# MotorCtrl.net
KiCad netlist of a schematic drawn in Altium Designer
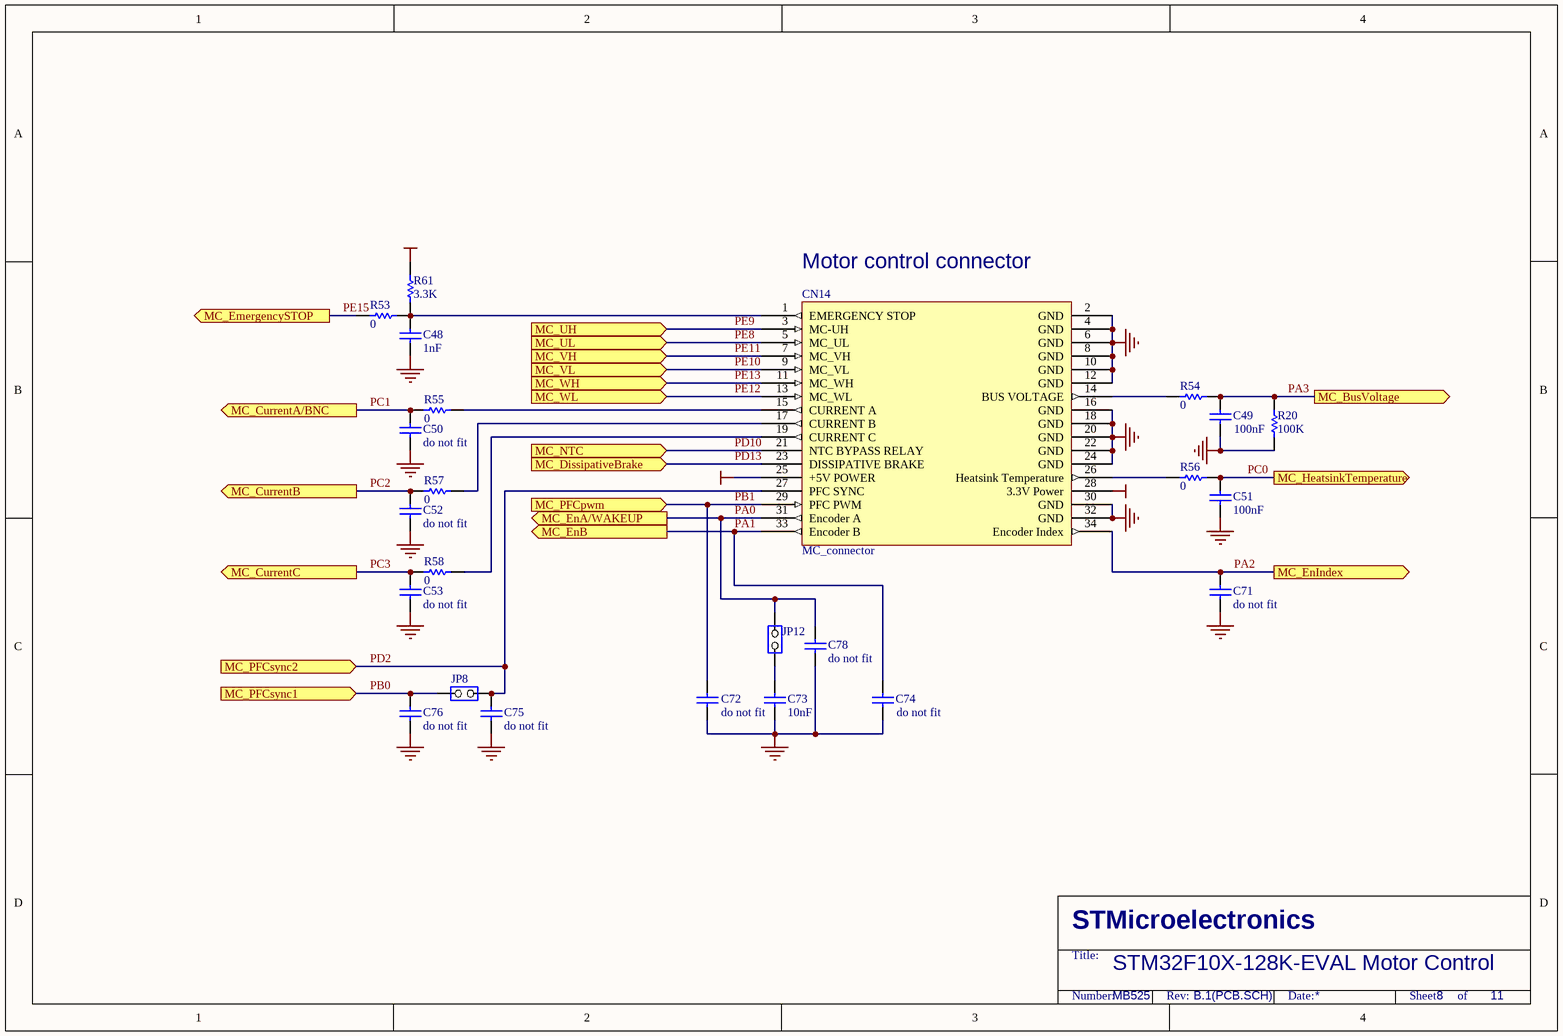
[diagram p0: MotorCtrl.SchDoc]

(export (version "E")
  (design (tool "Eeschema 10.0.6"))
  (components
    (comp (ref "C48")
      (value "1nF")
      (description "Capacitor")
      (fields (field (name "PUBLISHER") "Altium Limited"))
      (libsource (lib "Miscellaneous Devices") (part "CAP"))
    )
    (comp (ref "C49")
      (value "100nF")
      (description "Capacitor")
      (fields (field (name "PUBLISHER") "Altium Limited"))
      (libsource (lib "Miscellaneous Devices") (part "cap"))
    )
    (comp (ref "C50")
      (value "do not fit")
      (description "Capacitor")
      (fields (field (name "PUBLISHER") "Altium Limited"))
      (libsource (lib "Miscellaneous Devices") (part "cap"))
    )
    (comp (ref "C51")
      (value "100nF")
      (description "Capacitor")
      (fields (field (name "PUBLISHER") "Altium Limited"))
      (libsource (lib "Miscellaneous Devices") (part "cap"))
    )
    (comp (ref "C52")
      (value "do not fit")
      (description "Capacitor")
      (fields (field (name "PUBLISHER") "Altium Limited"))
      (libsource (lib "Miscellaneous Devices") (part "cap"))
    )
    (comp (ref "C53")
      (value "do not fit")
      (description "Capacitor")
      (fields (field (name "PUBLISHER") "Altium Limited"))
      (libsource (lib "Miscellaneous Devices") (part "cap"))
    )
    (comp (ref "C71")
      (value "do not fit")
      (description "Capacitor")
      (fields (field (name "PUBLISHER") "Altium Limited"))
      (libsource (lib "Miscellaneous Devices") (part "cap"))
    )
    (comp (ref "C72")
      (value "do not fit")
      (description "Capacitor")
      (fields (field (name "PUBLISHER") "Altium Limited"))
      (libsource (lib "Miscellaneous Devices") (part "cap"))
    )
    (comp (ref "C73")
      (value "10nF")
      (description "Capacitor")
      (fields (field (name "PUBLISHER") "Altium Limited"))
      (libsource (lib "Miscellaneous Devices") (part "cap"))
    )
    (comp (ref "C74")
      (value "do not fit")
      (description "Capacitor")
      (fields (field (name "PUBLISHER") "Altium Limited"))
      (libsource (lib "Miscellaneous Devices") (part "cap"))
    )
    (comp (ref "C75")
      (value "do not fit")
      (description "Capacitor")
      (fields (field (name "PUBLISHER") "Altium Limited"))
      (libsource (lib "Miscellaneous Devices") (part "cap"))
    )
    (comp (ref "C76")
      (value "do not fit")
      (description "Capacitor")
      (fields (field (name "PUBLISHER") "Altium Limited"))
      (libsource (lib "Miscellaneous Devices") (part "cap"))
    )
    (comp (ref "C78")
      (value "do not fit")
      (description "Capacitor")
      (fields (field (name "PUBLISHER") "Altium Limited"))
      (libsource (lib "Miscellaneous Devices") (part "cap"))
    )
    (comp (ref "CN14")
      (value "MC_connector")
      (footprint "IDC34S")
      (libsource (lib "MB525") (part "MC_connector"))
    )
    (comp (ref "JP8") (value "~") (footprint "SIP2") (libsource (lib "*") (part "JP2")))
    (comp (ref "JP12") (value "~") (footprint "SIP2") (libsource (lib "*") (part "JP2")))
    (comp (ref "R20")
      (value "100K")
      (footprint "0603")
      (description "Resistor")
      (fields (field (name "PUBLISHER") "Altium Limited"))
      (libsource (lib "Miscellaneous Devices") (part "Res1"))
    )
    (comp (ref "R53")
      (value "0")
      (description "Resistor")
      (fields (field (name "PUBLISHER") "Altium Limited"))
      (libsource (lib "Miscellaneous Devices") (part "Res1"))
    )
    (comp (ref "R54")
      (value "0")
      (footprint "0603")
      (description "Resistor")
      (fields (field (name "PUBLISHER") "Altium Limited"))
      (libsource (lib "Miscellaneous Devices") (part "Res1"))
    )
    (comp (ref "R55")
      (value "0")
      (footprint "0603")
      (description "Resistor")
      (fields (field (name "PUBLISHER") "Altium Limited"))
      (libsource (lib "Miscellaneous Devices") (part "Res1"))
    )
    (comp (ref "R56")
      (value "0")
      (footprint "0603")
      (description "Resistor")
      (fields (field (name "PUBLISHER") "Altium Limited"))
      (libsource (lib "Miscellaneous Devices") (part "Res1"))
    )
    (comp (ref "R57")
      (value "0")
      (footprint "0603")
      (description "Resistor")
      (fields (field (name "PUBLISHER") "Altium Limited"))
      (libsource (lib "Miscellaneous Devices") (part "Res1"))
    )
    (comp (ref "R58")
      (value "0")
      (footprint "0603")
      (description "Resistor")
      (fields (field (name "PUBLISHER") "Altium Limited"))
      (libsource (lib "Miscellaneous Devices") (part "Res1"))
    )
    (comp (ref "R61")
      (value "3.3K")
      (description "Resistor")
      (fields (field (name "PUBLISHER") "Altium Limited"))
      (libsource (lib "Miscellaneous Devices") (part "Res1"))
    )
  )
  (nets
    (net (code "1") (name "+3V3") (class "Default")
      (node (ref "CN14") (pin "28") (pinfunction "3.3V_Power_28") (pintype "power_in"))
      (node (ref "R61") (pin "2") (pinfunction "2_2") (pintype "passive"))
    )
    (net (code "2") (name "+5V") (class "Default")
      (node (ref "CN14") (pin "25") (pinfunction "+5V_POWER_25") (pintype "power_in"))
    )
    (net (code "3") (name "/PA0") (class "Default")
      (node (ref "C78") (pin "2") (pinfunction "2_2") (pintype "passive"))
      (node (ref "CN14") (pin "31") (pinfunction "Encoder_A_31") (pintype "output"))
      (node (ref "JP12") (pin "1") (pinfunction "COMMON_1") (pintype "passive"))
    )
    (net (code "4") (name "/PA1") (class "Default")
      (node (ref "C74") (pin "2") (pinfunction "2_2") (pintype "passive"))
      (node (ref "CN14") (pin "33") (pinfunction "Encoder_B_33") (pintype "output"))
    )
    (net (code "5") (name "/PA2") (class "Default")
      (node (ref "C71") (pin "2") (pinfunction "2_2") (pintype "passive"))
      (node (ref "CN14") (pin "34") (pinfunction "Encoder_Index_34") (pintype "output"))
    )
    (net (code "6") (name "/PA3") (class "Default")
      (node (ref "C49") (pin "2") (pinfunction "2_2") (pintype "passive"))
      (node (ref "R20") (pin "2") (pinfunction "2_2") (pintype "passive"))
      (node (ref "R54") (pin "2") (pinfunction "2_2") (pintype "passive"))
    )
    (net (code "7") (name "/PB0") (class "Default")
      (node (ref "C76") (pin "2") (pinfunction "2_2") (pintype "passive"))
      (node (ref "JP8") (pin "2") (pinfunction "NO_2") (pintype "passive"))
    )
    (net (code "8") (name "/PB1") (class "Default")
      (node (ref "C72") (pin "2") (pinfunction "2_2") (pintype "passive"))
      (node (ref "CN14") (pin "29") (pinfunction "PFC_PWM_29") (pintype "input"))
    )
    (net (code "9") (name "/PC0") (class "Default")
      (node (ref "C51") (pin "2") (pinfunction "2_2") (pintype "passive"))
      (node (ref "R56") (pin "2") (pinfunction "2_2") (pintype "passive"))
    )
    (net (code "10") (name "/PC1") (class "Default")
      (node (ref "C50") (pin "2") (pinfunction "2_2") (pintype "passive"))
      (node (ref "R55") (pin "1") (pinfunction "1_1") (pintype "passive"))
    )
    (net (code "11") (name "/PC2") (class "Default")
      (node (ref "C52") (pin "2") (pinfunction "2_2") (pintype "passive"))
      (node (ref "R57") (pin "1") (pinfunction "1_1") (pintype "passive"))
    )
    (net (code "12") (name "/PC3") (class "Default")
      (node (ref "C53") (pin "2") (pinfunction "2_2") (pintype "passive"))
      (node (ref "R58") (pin "1") (pinfunction "1_1") (pintype "passive"))
    )
    (net (code "13") (name "/PD2") (class "Default")
      (node (ref "C75") (pin "2") (pinfunction "2_2") (pintype "passive"))
      (node (ref "CN14") (pin "27") (pinfunction "PFC_SYNC_27") (pintype "passive"))
      (node (ref "JP8") (pin "1") (pinfunction "COMMON_1") (pintype "passive"))
    )
    (net (code "14") (name "/PD10") (class "Default")
      (node (ref "CN14") (pin "21") (pinfunction "NTC_BYPASS_RELAY_21") (pintype "passive"))
    )
    (net (code "15") (name "/PD13") (class "Default")
      (node (ref "CN14") (pin "23") (pinfunction "DISSIPATIVE_BRAKE_23") (pintype "passive"))
    )
    (net (code "16") (name "/PE8") (class "Default")
      (node (ref "CN14") (pin "5") (pinfunction "MC_UL_5") (pintype "input"))
    )
    (net (code "17") (name "/PE9") (class "Default")
      (node (ref "CN14") (pin "3") (pinfunction "MC-UH_3") (pintype "input"))
    )
    (net (code "18") (name "/PE10") (class "Default")
      (node (ref "CN14") (pin "9") (pinfunction "MC_VL_9") (pintype "input"))
    )
    (net (code "19") (name "/PE11") (class "Default")
      (node (ref "CN14") (pin "7") (pinfunction "MC_VH_7") (pintype "input"))
    )
    (net (code "20") (name "/PE12") (class "Default")
      (node (ref "CN14") (pin "13") (pinfunction "MC_WL_13") (pintype "input"))
    )
    (net (code "21") (name "/PE13") (class "Default")
      (node (ref "CN14") (pin "11") (pinfunction "MC_WH_11") (pintype "input"))
    )
    (net (code "22") (name "/PE15") (class "Default")
      (node (ref "R53") (pin "2") (pinfunction "2_2") (pintype "passive"))
    )
    (net (code "23") (name "GND") (class "Default")
      (node (ref "C48") (pin "1") (pinfunction "1_1") (pintype "passive"))
      (node (ref "C49") (pin "1") (pinfunction "1_1") (pintype "passive"))
      (node (ref "C50") (pin "1") (pinfunction "1_1") (pintype "passive"))
      (node (ref "C51") (pin "1") (pinfunction "1_1") (pintype "passive"))
      (node (ref "C52") (pin "1") (pinfunction "1_1") (pintype "passive"))
      (node (ref "C53") (pin "1") (pinfunction "1_1") (pintype "passive"))
      (node (ref "C71") (pin "1") (pinfunction "1_1") (pintype "passive"))
      (node (ref "C72") (pin "1") (pinfunction "1_1") (pintype "passive"))
      (node (ref "C73") (pin "1") (pinfunction "1_1") (pintype "passive"))
      (node (ref "C74") (pin "1") (pinfunction "1_1") (pintype "passive"))
      (node (ref "C75") (pin "1") (pinfunction "1_1") (pintype "passive"))
      (node (ref "C76") (pin "1") (pinfunction "1_1") (pintype "passive"))
      (node (ref "C78") (pin "1") (pinfunction "1_1") (pintype "passive"))
      (node (ref "CN14") (pin "10") (pinfunction "GND_10") (pintype "power_in"))
      (node (ref "CN14") (pin "12") (pinfunction "GND_12") (pintype "power_in"))
      (node (ref "CN14") (pin "16") (pinfunction "GND_16") (pintype "power_in"))
      (node (ref "CN14") (pin "18") (pinfunction "GND_18") (pintype "power_in"))
      (node (ref "CN14") (pin "2") (pinfunction "GND_2") (pintype "power_in"))
      (node (ref "CN14") (pin "20") (pinfunction "GND_20") (pintype "power_in"))
      (node (ref "CN14") (pin "22") (pinfunction "GND_22") (pintype "power_in"))
      (node (ref "CN14") (pin "24") (pinfunction "GND_24") (pintype "power_in"))
      (node (ref "CN14") (pin "30") (pinfunction "GND_30") (pintype "power_in"))
      (node (ref "CN14") (pin "32") (pinfunction "GND_32") (pintype "power_in"))
      (node (ref "CN14") (pin "4") (pinfunction "GND_4") (pintype "power_in"))
      (node (ref "CN14") (pin "6") (pinfunction "GND_6") (pintype "power_in"))
      (node (ref "CN14") (pin "8") (pinfunction "GND_8") (pintype "power_in"))
      (node (ref "R20") (pin "1") (pinfunction "1_1") (pintype "passive"))
    )
    (net (code "24") (name "Net-(CN14-BUS_VOLTAGE)") (class "Default")
      (node (ref "CN14") (pin "14") (pinfunction "BUS_VOLTAGE_14") (pintype "output"))
      (node (ref "R54") (pin "1") (pinfunction "1_1") (pintype "passive"))
    )
    (net (code "25") (name "Net-(CN14-CURRENT_A)") (class "Default")
      (node (ref "CN14") (pin "15") (pinfunction "CURRENT_A_15") (pintype "output"))
      (node (ref "R55") (pin "2") (pinfunction "2_2") (pintype "passive"))
    )
    (net (code "26") (name "Net-(CN14-CURRENT_B)") (class "Default")
      (node (ref "CN14") (pin "17") (pinfunction "CURRENT_B_17") (pintype "output"))
      (node (ref "R57") (pin "2") (pinfunction "2_2") (pintype "passive"))
    )
    (net (code "27") (name "Net-(CN14-CURRENT_C)") (class "Default")
      (node (ref "CN14") (pin "19") (pinfunction "CURRENT_C_19") (pintype "output"))
      (node (ref "R58") (pin "2") (pinfunction "2_2") (pintype "passive"))
    )
    (net (code "28") (name "Net-(CN14-EMERGENCY_STOP)") (class "Default")
      (node (ref "C48") (pin "2") (pinfunction "2_2") (pintype "passive"))
      (node (ref "CN14") (pin "1") (pinfunction "EMERGENCY_STOP_1") (pintype "output"))
      (node (ref "R53") (pin "1") (pinfunction "1_1") (pintype "passive"))
      (node (ref "R61") (pin "1") (pinfunction "1_1") (pintype "passive"))
    )
    (net (code "29") (name "Net-(CN14-Heatsink_Temperature)") (class "Default")
      (node (ref "CN14") (pin "26") (pinfunction "Heatsink_Temperature_26") (pintype "output"))
      (node (ref "R56") (pin "1") (pinfunction "1_1") (pintype "passive"))
    )
    (net (code "30") (name "Net-(JP12-NO)") (class "Default")
      (node (ref "C73") (pin "2") (pinfunction "2_2") (pintype "passive"))
      (node (ref "JP12") (pin "2") (pinfunction "NO_2") (pintype "passive"))
    )
  )
)
